# 04_DISCRETE_MIXER_IQ.net
KiCad netlist of a schematic drawn in Altium Designer
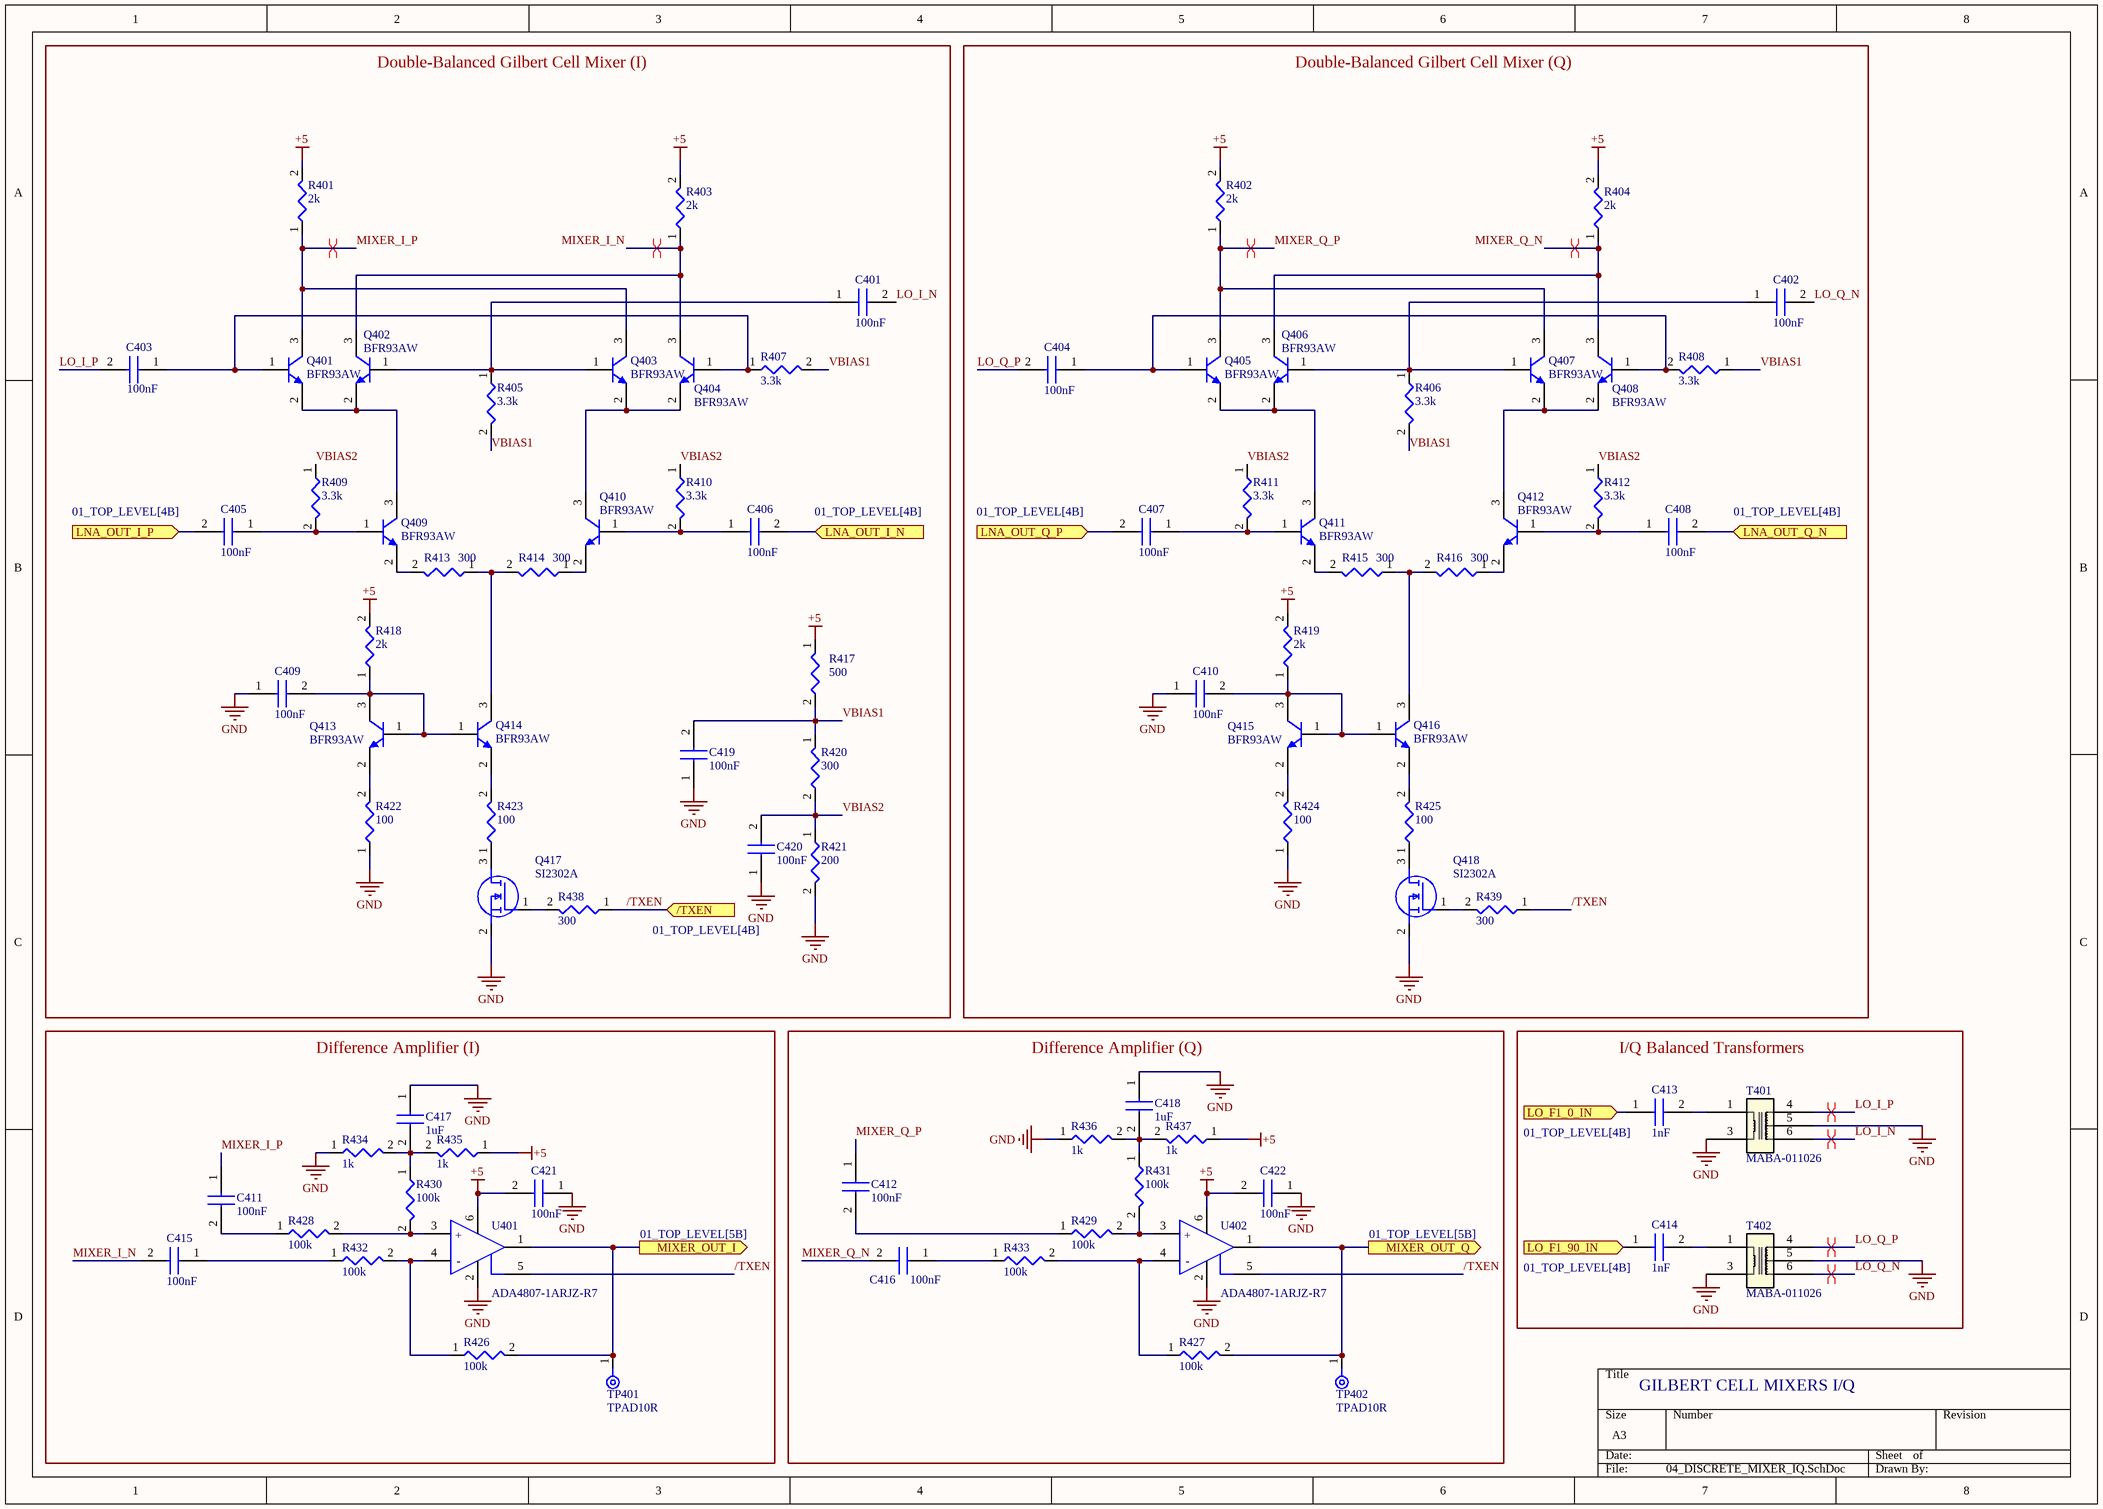
[diagram p0: 04_DISCRETE_MIXER_IQ.SchDoc]

(export (version "E")
  (design (tool "Eeschema 10.0.6"))
  (components
    (comp (ref "C401")
      (value "100nF")
      (footprint "CAP_0805")
      (description "Capacitor SMD 0805")
      (libsource (lib "Passive_Components") (part "CAP_0805"))
    )
    (comp (ref "C402")
      (value "100nF")
      (footprint "CAP_0805")
      (description "Capacitor SMD 0805")
      (libsource (lib "Passive_Components") (part "CAP_0805"))
    )
    (comp (ref "C403")
      (value "100nF")
      (footprint "CAP_0805")
      (description "Capacitor SMD 0805")
      (libsource (lib "Passive_Components") (part "CAP_0805"))
    )
    (comp (ref "C404")
      (value "100nF")
      (footprint "CAP_0805")
      (description "Capacitor SMD 0805")
      (libsource (lib "Passive_Components") (part "CAP_0805"))
    )
    (comp (ref "C405")
      (value "100nF")
      (footprint "CAP_0805")
      (description "Capacitor SMD 0805")
      (libsource (lib "Passive_Components") (part "CAP_0805"))
    )
    (comp (ref "C406")
      (value "100nF")
      (footprint "CAP_0805")
      (description "Capacitor SMD 0805")
      (libsource (lib "Passive_Components") (part "CAP_0805"))
    )
    (comp (ref "C407")
      (value "100nF")
      (footprint "CAP_0805")
      (description "Capacitor SMD 0805")
      (libsource (lib "Passive_Components") (part "CAP_0805"))
    )
    (comp (ref "C408")
      (value "100nF")
      (footprint "CAP_0805")
      (description "Capacitor SMD 0805")
      (libsource (lib "Passive_Components") (part "CAP_0805"))
    )
    (comp (ref "C409")
      (value "100nF")
      (footprint "CAP_0805")
      (description "Capacitor SMD 0805")
      (libsource (lib "Passive_Components") (part "CAP_0805"))
    )
    (comp (ref "C410")
      (value "100nF")
      (footprint "CAP_0805")
      (description "Capacitor SMD 0805")
      (libsource (lib "Passive_Components") (part "CAP_0805"))
    )
    (comp (ref "C411")
      (value "100nF")
      (footprint "CAP_0805")
      (description "Capacitor SMD 0805")
      (libsource (lib "Passive_Components") (part "CAP_0805"))
    )
    (comp (ref "C412")
      (value "100nF")
      (footprint "CAP_0805")
      (description "Capacitor SMD 0805")
      (libsource (lib "Passive_Components") (part "CAP_0805"))
    )
    (comp (ref "C413")
      (value "1nF")
      (footprint "CAP_0805")
      (description "Capacitor SMD 0805")
      (libsource (lib "Passive_Components") (part "CAP_0805"))
    )
    (comp (ref "C414")
      (value "1nF")
      (footprint "CAP_0805")
      (description "Capacitor SMD 0805")
      (libsource (lib "Passive_Components") (part "CAP_0805"))
    )
    (comp (ref "C415")
      (value "100nF")
      (footprint "CAP_0805")
      (description "Capacitor SMD 0805")
      (libsource (lib "Passive_Components") (part "CAP_0805"))
    )
    (comp (ref "C416")
      (value "100nF")
      (footprint "CAP_0805")
      (description "Capacitor SMD 0805")
      (libsource (lib "Passive_Components") (part "CAP_0805"))
    )
    (comp (ref "C417")
      (value "1uF")
      (footprint "CAP_0805")
      (description "Capacitor SMD 0805")
      (libsource (lib "Passive_Components") (part "CAP_0805"))
    )
    (comp (ref "C418")
      (value "1uF")
      (footprint "CAP_0805")
      (description "Capacitor SMD 0805")
      (libsource (lib "Passive_Components") (part "CAP_0805"))
    )
    (comp (ref "C419")
      (value "100nF")
      (footprint "CAP_0805")
      (description "Capacitor SMD 0805")
      (libsource (lib "Passive_Components") (part "CAP_0805"))
    )
    (comp (ref "C420")
      (value "100nF")
      (footprint "CAP_0805")
      (description "Capacitor SMD 0805")
      (libsource (lib "Passive_Components") (part "CAP_0805"))
    )
    (comp (ref "C421")
      (value "100nF")
      (footprint "CAP_0805")
      (description "Capacitor SMD 0805")
      (libsource (lib "Passive_Components") (part "CAP_0805"))
    )
    (comp (ref "C422")
      (value "100nF")
      (footprint "CAP_0805")
      (description "Capacitor SMD 0805")
      (libsource (lib "Passive_Components") (part "CAP_0805"))
    )
    (comp (ref "Q401")
      (value "BFR93AW")
      (footprint "INF-SOT323_M")
      (description "NPN Silicon RF Transistor, 12 V VCEO, 90 mA IC, 15.5 dB Gmax, SOT323, Green")
      (fields (field (name "MANUFACTURER") "Infineon"))
      (libsource (lib "Altium Content Vault") (part "INF-BFR93AW-3"))
    )
    (comp (ref "Q402")
      (value "BFR93AW")
      (footprint "INF-SOT323_M")
      (description "NPN Silicon RF Transistor, 12 V VCEO, 90 mA IC, 15.5 dB Gmax, SOT323, Green")
      (fields (field (name "MANUFACTURER") "Infineon"))
      (libsource (lib "Altium Content Vault") (part "INF-BFR93AW-3"))
    )
    (comp (ref "Q403")
      (value "BFR93AW")
      (footprint "INF-SOT323_M")
      (description "NPN Silicon RF Transistor, 12 V VCEO, 90 mA IC, 15.5 dB Gmax, SOT323, Green")
      (fields (field (name "MANUFACTURER") "Infineon"))
      (libsource (lib "Altium Content Vault") (part "INF-BFR93AW-3"))
    )
    (comp (ref "Q404")
      (value "BFR93AW")
      (footprint "INF-SOT323_M")
      (description "NPN Silicon RF Transistor, 12 V VCEO, 90 mA IC, 15.5 dB Gmax, SOT323, Green")
      (fields (field (name "MANUFACTURER") "Infineon"))
      (libsource (lib "Altium Content Vault") (part "INF-BFR93AW-3"))
    )
    (comp (ref "Q405")
      (value "BFR93AW")
      (footprint "INF-SOT323_M")
      (description "NPN Silicon RF Transistor, 12 V VCEO, 90 mA IC, 15.5 dB Gmax, SOT323, Green")
      (fields (field (name "MANUFACTURER") "Infineon"))
      (libsource (lib "Altium Content Vault") (part "INF-BFR93AW-3"))
    )
    (comp (ref "Q406")
      (value "BFR93AW")
      (footprint "INF-SOT323_M")
      (description "NPN Silicon RF Transistor, 12 V VCEO, 90 mA IC, 15.5 dB Gmax, SOT323, Green")
      (fields (field (name "MANUFACTURER") "Infineon"))
      (libsource (lib "Altium Content Vault") (part "INF-BFR93AW-3"))
    )
    (comp (ref "Q407")
      (value "BFR93AW")
      (footprint "INF-SOT323_M")
      (description "NPN Silicon RF Transistor, 12 V VCEO, 90 mA IC, 15.5 dB Gmax, SOT323, Green")
      (fields (field (name "MANUFACTURER") "Infineon"))
      (libsource (lib "Altium Content Vault") (part "INF-BFR93AW-3"))
    )
    (comp (ref "Q408")
      (value "BFR93AW")
      (footprint "INF-SOT323_M")
      (description "NPN Silicon RF Transistor, 12 V VCEO, 90 mA IC, 15.5 dB Gmax, SOT323, Green")
      (fields (field (name "MANUFACTURER") "Infineon"))
      (libsource (lib "Altium Content Vault") (part "INF-BFR93AW-3"))
    )
    (comp (ref "Q409")
      (value "BFR93AW")
      (footprint "INF-SOT323_M")
      (description "NPN Silicon RF Transistor, 12 V VCEO, 90 mA IC, 15.5 dB Gmax, SOT323, Green")
      (fields (field (name "MANUFACTURER") "Infineon"))
      (libsource (lib "Altium Content Vault") (part "INF-BFR93AW-3"))
    )
    (comp (ref "Q410")
      (value "BFR93AW")
      (footprint "INF-SOT323_M")
      (description "NPN Silicon RF Transistor, 12 V VCEO, 90 mA IC, 15.5 dB Gmax, SOT323, Green")
      (fields (field (name "MANUFACTURER") "Infineon"))
      (libsource (lib "Altium Content Vault") (part "INF-BFR93AW-3"))
    )
    (comp (ref "Q411")
      (value "BFR93AW")
      (footprint "INF-SOT323_M")
      (description "NPN Silicon RF Transistor, 12 V VCEO, 90 mA IC, 15.5 dB Gmax, SOT323, Green")
      (fields (field (name "MANUFACTURER") "Infineon"))
      (libsource (lib "Altium Content Vault") (part "INF-BFR93AW-3"))
    )
    (comp (ref "Q412")
      (value "BFR93AW")
      (footprint "INF-SOT323_M")
      (description "NPN Silicon RF Transistor, 12 V VCEO, 90 mA IC, 15.5 dB Gmax, SOT323, Green")
      (fields (field (name "MANUFACTURER") "Infineon"))
      (libsource (lib "Altium Content Vault") (part "INF-BFR93AW-3"))
    )
    (comp (ref "Q413")
      (value "BFR93AW")
      (footprint "INF-SOT323_M")
      (description "NPN Silicon RF Transistor, 12 V VCEO, 90 mA IC, 15.5 dB Gmax, SOT323, Green")
      (fields (field (name "MANUFACTURER") "Infineon"))
      (libsource (lib "Altium Content Vault") (part "INF-BFR93AW-3"))
    )
    (comp (ref "Q414")
      (value "BFR93AW")
      (footprint "INF-SOT323_M")
      (description "NPN Silicon RF Transistor, 12 V VCEO, 90 mA IC, 15.5 dB Gmax, SOT323, Green")
      (fields (field (name "MANUFACTURER") "Infineon"))
      (libsource (lib "Altium Content Vault") (part "INF-BFR93AW-3"))
    )
    (comp (ref "Q415")
      (value "BFR93AW")
      (footprint "INF-SOT323_M")
      (description "NPN Silicon RF Transistor, 12 V VCEO, 90 mA IC, 15.5 dB Gmax, SOT323, Green")
      (fields (field (name "MANUFACTURER") "Infineon"))
      (libsource (lib "Altium Content Vault") (part "INF-BFR93AW-3"))
    )
    (comp (ref "Q416")
      (value "BFR93AW")
      (footprint "INF-SOT323_M")
      (description "NPN Silicon RF Transistor, 12 V VCEO, 90 mA IC, 15.5 dB Gmax, SOT323, Green")
      (fields (field (name "MANUFACTURER") "Infineon"))
      (libsource (lib "Altium Content Vault") (part "INF-BFR93AW-3"))
    )
    (comp (ref "Q417")
      (value "SI2302A")
      (footprint "SamacSys:SOT95P237X112-3N")
      (description "MOSFET (N-Channel)")
      (libsource (lib "*") (part "SI2302ADS"))
    )
    (comp (ref "Q418")
      (value "SI2302A")
      (footprint "SamacSys:SOT95P237X112-3N")
      (description "MOSFET (N-Channel)")
      (libsource (lib "*") (part "SI2302ADS"))
    )
    (comp (ref "R401")
      (value "2k")
      (footprint "RES_0805")
      (description "Resistor SMD 0805")
      (libsource (lib "Passive_Components") (part "RES_0805"))
    )
    (comp (ref "R402")
      (value "2k")
      (footprint "RES_0805")
      (description "Resistor SMD 0805")
      (libsource (lib "Passive_Components") (part "RES_0805"))
    )
    (comp (ref "R403")
      (value "2k")
      (footprint "RES_0805")
      (description "Resistor SMD 0805")
      (libsource (lib "Passive_Components") (part "RES_0805"))
    )
    (comp (ref "R404")
      (value "2k")
      (footprint "RES_0805")
      (description "Resistor SMD 0805")
      (libsource (lib "Passive_Components") (part "RES_0805"))
    )
    (comp (ref "R405")
      (value "3.3k")
      (footprint "RES_0805")
      (description "Resistor SMD 0805")
      (libsource (lib "Passive_Components") (part "RES_0805"))
    )
    (comp (ref "R406")
      (value "3.3k")
      (footprint "RES_0805")
      (description "Resistor SMD 0805")
      (libsource (lib "Passive_Components") (part "RES_0805"))
    )
    (comp (ref "R407")
      (value "3.3k")
      (footprint "RES_0805")
      (description "Resistor SMD 0805")
      (libsource (lib "Passive_Components") (part "RES_0805"))
    )
    (comp (ref "R408")
      (value "3.3k")
      (footprint "RES_0805")
      (description "Resistor SMD 0805")
      (libsource (lib "Passive_Components") (part "RES_0805"))
    )
    (comp (ref "R409")
      (value "3.3k")
      (footprint "RES_0805")
      (description "Resistor SMD 0805")
      (libsource (lib "Passive_Components") (part "RES_0805"))
    )
    (comp (ref "R410")
      (value "3.3k")
      (footprint "RES_0805")
      (description "Resistor SMD 0805")
      (libsource (lib "Passive_Components") (part "RES_0805"))
    )
    (comp (ref "R411")
      (value "3.3k")
      (footprint "RES_0805")
      (description "Resistor SMD 0805")
      (libsource (lib "Passive_Components") (part "RES_0805"))
    )
    (comp (ref "R412")
      (value "3.3k")
      (footprint "RES_0805")
      (description "Resistor SMD 0805")
      (libsource (lib "Passive_Components") (part "RES_0805"))
    )
    (comp (ref "R413")
      (value "300")
      (footprint "RES_0805")
      (description "Resistor SMD 0805")
      (libsource (lib "Passive_Components") (part "RES_0805"))
    )
    (comp (ref "R414")
      (value "300")
      (footprint "RES_0805")
      (description "Resistor SMD 0805")
      (libsource (lib "Passive_Components") (part "RES_0805"))
    )
    (comp (ref "R415")
      (value "300")
      (footprint "RES_0805")
      (description "Resistor SMD 0805")
      (libsource (lib "Passive_Components") (part "RES_0805"))
    )
    (comp (ref "R416")
      (value "300")
      (footprint "RES_0805")
      (description "Resistor SMD 0805")
      (libsource (lib "Passive_Components") (part "RES_0805"))
    )
    (comp (ref "R417")
      (value "500")
      (footprint "RES_0805")
      (description "Resistor SMD 0805")
      (libsource (lib "Passive_Components") (part "RES_0805"))
    )
    (comp (ref "R418")
      (value "2k")
      (footprint "RES_0805")
      (description "Resistor SMD 0805")
      (libsource (lib "Passive_Components") (part "RES_0805"))
    )
    (comp (ref "R419")
      (value "2k")
      (footprint "RES_0805")
      (description "Resistor SMD 0805")
      (libsource (lib "Passive_Components") (part "RES_0805"))
    )
    (comp (ref "R420")
      (value "300")
      (footprint "RES_0805")
      (description "Resistor SMD 0805")
      (libsource (lib "Passive_Components") (part "RES_0805"))
    )
    (comp (ref "R421")
      (value "200")
      (footprint "RES_0805")
      (description "Resistor SMD 0805")
      (libsource (lib "Passive_Components") (part "RES_0805"))
    )
    (comp (ref "R422")
      (value "100")
      (footprint "RES_0805")
      (description "Resistor SMD 0805")
      (libsource (lib "Passive_Components") (part "RES_0805"))
    )
    (comp (ref "R423")
      (value "100")
      (footprint "RES_0805")
      (description "Resistor SMD 0805")
      (libsource (lib "Passive_Components") (part "RES_0805"))
    )
    (comp (ref "R424")
      (value "100")
      (footprint "RES_0805")
      (description "Resistor SMD 0805")
      (libsource (lib "Passive_Components") (part "RES_0805"))
    )
    (comp (ref "R425")
      (value "100")
      (footprint "RES_0805")
      (description "Resistor SMD 0805")
      (libsource (lib "Passive_Components") (part "RES_0805"))
    )
    (comp (ref "R426")
      (value "100k")
      (footprint "RES_0805")
      (description "Resistor SMD 0805")
      (libsource (lib "Passive_Components") (part "RES_0805"))
    )
    (comp (ref "R427")
      (value "100k")
      (footprint "RES_0805")
      (description "Resistor SMD 0805")
      (libsource (lib "Passive_Components") (part "RES_0805"))
    )
    (comp (ref "R428")
      (value "100k")
      (footprint "RES_0805")
      (description "Resistor SMD 0805")
      (libsource (lib "Passive_Components") (part "RES_0805"))
    )
    (comp (ref "R429")
      (value "100k")
      (footprint "RES_0805")
      (description "Resistor SMD 0805")
      (libsource (lib "Passive_Components") (part "RES_0805"))
    )
    (comp (ref "R430")
      (value "100k")
      (footprint "RES_0805")
      (description "Resistor SMD 0805")
      (libsource (lib "Passive_Components") (part "RES_0805"))
    )
    (comp (ref "R431")
      (value "100k")
      (footprint "RES_0805")
      (description "Resistor SMD 0805")
      (libsource (lib "Passive_Components") (part "RES_0805"))
    )
    (comp (ref "R432")
      (value "100k")
      (footprint "RES_0805")
      (description "Resistor SMD 0805")
      (libsource (lib "Passive_Components") (part "RES_0805"))
    )
    (comp (ref "R433")
      (value "100k")
      (footprint "RES_0805")
      (description "Resistor SMD 0805")
      (libsource (lib "Passive_Components") (part "RES_0805"))
    )
    (comp (ref "R434")
      (value "1k")
      (footprint "RES_0805")
      (description "Resistor SMD 0805")
      (libsource (lib "Passive_Components") (part "RES_0805"))
    )
    (comp (ref "R435")
      (value "1k")
      (footprint "RES_0805")
      (description "Resistor SMD 0805")
      (libsource (lib "Passive_Components") (part "RES_0805"))
    )
    (comp (ref "R436")
      (value "1k")
      (footprint "RES_0805")
      (description "Resistor SMD 0805")
      (libsource (lib "Passive_Components") (part "RES_0805"))
    )
    (comp (ref "R437")
      (value "1k")
      (footprint "RES_0805")
      (description "Resistor SMD 0805")
      (libsource (lib "Passive_Components") (part "RES_0805"))
    )
    (comp (ref "R438")
      (value "300")
      (footprint "RES_0805")
      (description "Resistor SMD 0805")
      (libsource (lib "Passive_Components") (part "RES_0805"))
    )
    (comp (ref "R439")
      (value "300")
      (footprint "RES_0805")
      (description "Resistor SMD 0805")
      (libsource (lib "Passive_Components") (part "RES_0805"))
    )
    (comp (ref "T401")
      (value "MABA-011026")
      (footprint "MABA-011026_MCM")
      (description "RF Transformer")
      (fields (field (name "COPYRIGHT") "Copyright (C) 2025 Ultra Librarian. All rights reserved."))
      (libsource (lib "PASSIVE_COMPONENTS") (part "MABA-011026"))
    )
    (comp (ref "T402")
      (value "MABA-011026")
      (footprint "MABA-011026_MCM")
      (description "RF Transformer")
      (fields (field (name "COPYRIGHT") "Copyright (C) 2025 Ultra Librarian. All rights reserved."))
      (libsource (lib "PASSIVE_COMPONENTS") (part "MABA-011026"))
    )
    (comp (ref "TP401")
      (value "TPAD10R")
      (footprint "TEST_POINT")
      (description "Testpont Pad 10R")
      (libsource (lib "PASSIVE_COMPONENTS") (part "TEST_POINT"))
    )
    (comp (ref "TP402")
      (value "TPAD10R")
      (footprint "TEST_POINT")
      (description "Testpont Pad 10R")
      (libsource (lib "PASSIVE_COMPONENTS") (part "TEST_POINT"))
    )
    (comp (ref "U401")
      (value "ADA4807-1ARJZ-R7")
      (footprint "FP-RJ-6-IPC_A")
      (description "IC OPAMP VFB 1 CIRCUIT SOT23-6")
      (libsource (lib "Altium Content Vault") (part "0cc169e61f44c0172c2773b4ba3b2c6"))
    )
    (comp (ref "U402")
      (value "ADA4807-1ARJZ-R7")
      (footprint "FP-RJ-6-IPC_A")
      (description "IC OPAMP VFB 1 CIRCUIT SOT23-6")
      (libsource (lib "Altium Content Vault") (part "0cc169e61f44c0172c2773b4ba3b2c6"))
    )
  )
  (nets
    (net (code "1") (name "+5") (class "Default")
      (node (ref "C421") (pin "2") (pinfunction "2_2") (pintype "passive"))
      (node (ref "C422") (pin "2") (pinfunction "2_2") (pintype "passive"))
      (node (ref "R401") (pin "2") (pinfunction "2_2") (pintype "passive"))
      (node (ref "R402") (pin "2") (pinfunction "2_2") (pintype "passive"))
      (node (ref "R403") (pin "2") (pinfunction "2_2") (pintype "passive"))
      (node (ref "R404") (pin "2") (pinfunction "2_2") (pintype "passive"))
      (node (ref "R417") (pin "1") (pinfunction "1_1") (pintype "passive"))
      (node (ref "R418") (pin "2") (pinfunction "2_2") (pintype "passive"))
      (node (ref "R419") (pin "2") (pinfunction "2_2") (pintype "passive"))
      (node (ref "R435") (pin "1") (pinfunction "1_1") (pintype "passive"))
      (node (ref "R437") (pin "1") (pinfunction "1_1") (pintype "passive"))
      (node (ref "U401") (pin "6") (pinfunction "+VS_6") (pintype "power_in"))
      (node (ref "U402") (pin "6") (pinfunction "+VS_6") (pintype "power_in"))
    )
    (net (code "2") (name "/LNA_OUT_I_N") (class "Default")
      (node (ref "C406") (pin "2") (pinfunction "2_2") (pintype "passive"))
    )
    (net (code "3") (name "/LNA_OUT_I_P") (class "Default")
      (node (ref "C405") (pin "2") (pinfunction "2_2") (pintype "passive"))
    )
    (net (code "4") (name "/LNA_OUT_Q_N") (class "Default")
      (node (ref "C408") (pin "2") (pinfunction "2_2") (pintype "passive"))
    )
    (net (code "5") (name "/LNA_OUT_Q_P") (class "Default")
      (node (ref "C407") (pin "2") (pinfunction "2_2") (pintype "passive"))
    )
    (net (code "6") (name "/LO_F1_0_IN") (class "Default")
      (node (ref "C413") (pin "1") (pinfunction "1_1") (pintype "passive"))
    )
    (net (code "7") (name "/LO_F1_90_IN") (class "Default")
      (node (ref "C414") (pin "1") (pinfunction "1_1") (pintype "passive"))
    )
    (net (code "8") (name "/LO_I_N") (class "Default")
      (node (ref "C401") (pin "2") (pinfunction "2_2") (pintype "passive"))
      (node (ref "T401") (pin "6") (pinfunction "6_6") (pintype "passive"))
    )
    (net (code "9") (name "/LO_I_P") (class "Default")
      (node (ref "C403") (pin "2") (pinfunction "2_2") (pintype "passive"))
      (node (ref "T401") (pin "4") (pinfunction "4_4") (pintype "passive"))
    )
    (net (code "10") (name "/LO_Q_N") (class "Default")
      (node (ref "C402") (pin "2") (pinfunction "2_2") (pintype "passive"))
      (node (ref "T402") (pin "6") (pinfunction "6_6") (pintype "passive"))
    )
    (net (code "11") (name "/LO_Q_P") (class "Default")
      (node (ref "C404") (pin "2") (pinfunction "2_2") (pintype "passive"))
      (node (ref "T402") (pin "4") (pinfunction "4_4") (pintype "passive"))
    )
    (net (code "12") (name "/MIXER_I_N") (class "Default")
      (node (ref "C415") (pin "2") (pinfunction "2_2") (pintype "passive"))
      (node (ref "Q402") (pin "3") (pinfunction "C_3") (pintype "passive"))
      (node (ref "Q404") (pin "3") (pinfunction "C_3") (pintype "passive"))
      (node (ref "R403") (pin "1") (pinfunction "1_1") (pintype "passive"))
    )
    (net (code "13") (name "/MIXER_I_P") (class "Default")
      (node (ref "C411") (pin "1") (pinfunction "1_1") (pintype "passive"))
      (node (ref "Q401") (pin "3") (pinfunction "C_3") (pintype "passive"))
      (node (ref "Q403") (pin "3") (pinfunction "C_3") (pintype "passive"))
      (node (ref "R401") (pin "1") (pinfunction "1_1") (pintype "passive"))
    )
    (net (code "14") (name "/MIXER_OUT_I") (class "Default")
      (node (ref "R426") (pin "2") (pinfunction "2_2") (pintype "passive"))
      (node (ref "TP401") (pin "1") (pinfunction "1_1") (pintype "passive"))
      (node (ref "U401") (pin "1") (pinfunction "VOUT_1") (pintype "passive"))
    )
    (net (code "15") (name "/MIXER_OUT_Q") (class "Default")
      (node (ref "R427") (pin "2") (pinfunction "2_2") (pintype "passive"))
      (node (ref "TP402") (pin "1") (pinfunction "1_1") (pintype "passive"))
      (node (ref "U402") (pin "1") (pinfunction "VOUT_1") (pintype "passive"))
    )
    (net (code "16") (name "/MIXER_Q_N") (class "Default")
      (node (ref "C416") (pin "2") (pinfunction "2_2") (pintype "passive"))
      (node (ref "Q406") (pin "3") (pinfunction "C_3") (pintype "passive"))
      (node (ref "Q408") (pin "3") (pinfunction "C_3") (pintype "passive"))
      (node (ref "R404") (pin "1") (pinfunction "1_1") (pintype "passive"))
    )
    (net (code "17") (name "/MIXER_Q_P") (class "Default")
      (node (ref "C412") (pin "1") (pinfunction "1_1") (pintype "passive"))
      (node (ref "Q405") (pin "3") (pinfunction "C_3") (pintype "passive"))
      (node (ref "Q407") (pin "3") (pinfunction "C_3") (pintype "passive"))
      (node (ref "R402") (pin "1") (pinfunction "1_1") (pintype "passive"))
    )
    (net (code "18") (name "/VBIAS1") (class "Default")
      (node (ref "C419") (pin "2") (pinfunction "2_2") (pintype "passive"))
      (node (ref "R405") (pin "2") (pinfunction "2_2") (pintype "passive"))
      (node (ref "R406") (pin "2") (pinfunction "2_2") (pintype "passive"))
      (node (ref "R407") (pin "2") (pinfunction "2_2") (pintype "passive"))
      (node (ref "R408") (pin "1") (pinfunction "1_1") (pintype "passive"))
      (node (ref "R417") (pin "2") (pinfunction "2_2") (pintype "passive"))
      (node (ref "R420") (pin "1") (pinfunction "1_1") (pintype "passive"))
    )
    (net (code "19") (name "/VBIAS2") (class "Default")
      (node (ref "C420") (pin "2") (pinfunction "2_2") (pintype "passive"))
      (node (ref "R409") (pin "1") (pinfunction "1_1") (pintype "passive"))
      (node (ref "R410") (pin "1") (pinfunction "1_1") (pintype "passive"))
      (node (ref "R411") (pin "1") (pinfunction "1_1") (pintype "passive"))
      (node (ref "R412") (pin "1") (pinfunction "1_1") (pintype "passive"))
      (node (ref "R420") (pin "2") (pinfunction "2_2") (pintype "passive"))
      (node (ref "R421") (pin "1") (pinfunction "1_1") (pintype "passive"))
    )
    (net (code "20") (name "/{slash}TXEN") (class "Default")
      (node (ref "R438") (pin "1") (pinfunction "1_1") (pintype "passive"))
      (node (ref "R439") (pin "1") (pinfunction "1_1") (pintype "passive"))
      (node (ref "U401") (pin "5") (pinfunction "~{DISABLE}_5") (pintype "passive"))
      (node (ref "U402") (pin "5") (pinfunction "~{DISABLE}_5") (pintype "passive"))
    )
    (net (code "21") (name "GND") (class "Default")
      (node (ref "C409") (pin "1") (pinfunction "1_1") (pintype "passive"))
      (node (ref "C410") (pin "1") (pinfunction "1_1") (pintype "passive"))
      (node (ref "C417") (pin "1") (pinfunction "1_1") (pintype "passive"))
      (node (ref "C418") (pin "1") (pinfunction "1_1") (pintype "passive"))
      (node (ref "C419") (pin "1") (pinfunction "1_1") (pintype "passive"))
      (node (ref "C420") (pin "1") (pinfunction "1_1") (pintype "passive"))
      (node (ref "C421") (pin "1") (pinfunction "1_1") (pintype "passive"))
      (node (ref "C422") (pin "1") (pinfunction "1_1") (pintype "passive"))
      (node (ref "Q417") (pin "2") (pinfunction "S_2") (pintype "passive"))
      (node (ref "Q418") (pin "2") (pinfunction "S_2") (pintype "passive"))
      (node (ref "R421") (pin "2") (pinfunction "2_2") (pintype "passive"))
      (node (ref "R422") (pin "1") (pinfunction "1_1") (pintype "passive"))
      (node (ref "R424") (pin "1") (pinfunction "1_1") (pintype "passive"))
      (node (ref "R434") (pin "1") (pinfunction "1_1") (pintype "passive"))
      (node (ref "R436") (pin "1") (pinfunction "1_1") (pintype "passive"))
      (node (ref "T401") (pin "3") (pinfunction "3_3") (pintype "passive"))
      (node (ref "T401") (pin "5") (pinfunction "5_5") (pintype "passive"))
      (node (ref "T402") (pin "3") (pinfunction "3_3") (pintype "passive"))
      (node (ref "T402") (pin "5") (pinfunction "5_5") (pintype "passive"))
      (node (ref "U401") (pin "2") (pinfunction "-VS_2") (pintype "power_in"))
      (node (ref "U402") (pin "2") (pinfunction "-VS_2") (pintype "power_in"))
    )
    (net (code "22") (name "Net-(C411-Pad2)") (class "Default")
      (node (ref "C411") (pin "2") (pinfunction "2_2") (pintype "passive"))
      (node (ref "R428") (pin "1") (pinfunction "1_1") (pintype "passive"))
    )
    (net (code "23") (name "Net-(C412-Pad2)") (class "Default")
      (node (ref "C412") (pin "2") (pinfunction "2_2") (pintype "passive"))
      (node (ref "R429") (pin "1") (pinfunction "1_1") (pintype "passive"))
    )
    (net (code "24") (name "Net-(C413-Pad2)") (class "Default")
      (node (ref "C413") (pin "2") (pinfunction "2_2") (pintype "passive"))
      (node (ref "T401") (pin "1") (pinfunction "1_1") (pintype "passive"))
    )
    (net (code "25") (name "Net-(C414-Pad2)") (class "Default")
      (node (ref "C414") (pin "2") (pinfunction "2_2") (pintype "passive"))
      (node (ref "T402") (pin "1") (pinfunction "1_1") (pintype "passive"))
    )
    (net (code "26") (name "Net-(C415-Pad1)") (class "Default")
      (node (ref "C415") (pin "1") (pinfunction "1_1") (pintype "passive"))
      (node (ref "R432") (pin "1") (pinfunction "1_1") (pintype "passive"))
    )
    (net (code "27") (name "Net-(C416-Pad1)") (class "Default")
      (node (ref "C416") (pin "1") (pinfunction "1_1") (pintype "passive"))
      (node (ref "R433") (pin "1") (pinfunction "1_1") (pintype "passive"))
    )
    (net (code "28") (name "Net-(C417-Pad2)") (class "Default")
      (node (ref "C417") (pin "2") (pinfunction "2_2") (pintype "passive"))
      (node (ref "R430") (pin "1") (pinfunction "1_1") (pintype "passive"))
      (node (ref "R434") (pin "2") (pinfunction "2_2") (pintype "passive"))
      (node (ref "R435") (pin "2") (pinfunction "2_2") (pintype "passive"))
    )
    (net (code "29") (name "Net-(C418-Pad2)") (class "Default")
      (node (ref "C418") (pin "2") (pinfunction "2_2") (pintype "passive"))
      (node (ref "R431") (pin "1") (pinfunction "1_1") (pintype "passive"))
      (node (ref "R436") (pin "2") (pinfunction "2_2") (pintype "passive"))
      (node (ref "R437") (pin "2") (pinfunction "2_2") (pintype "passive"))
    )
    (net (code "30") (name "Net-(Q401-B)") (class "Default")
      (node (ref "C403") (pin "1") (pinfunction "1_1") (pintype "passive"))
      (node (ref "Q401") (pin "1") (pinfunction "B_1") (pintype "passive"))
      (node (ref "Q404") (pin "1") (pinfunction "B_1") (pintype "passive"))
      (node (ref "R407") (pin "1") (pinfunction "1_1") (pintype "passive"))
    )
    (net (code "31") (name "Net-(Q401-E)") (class "Default")
      (node (ref "Q401") (pin "2") (pinfunction "E_2") (pintype "passive"))
      (node (ref "Q402") (pin "2") (pinfunction "E_2") (pintype "passive"))
      (node (ref "Q409") (pin "3") (pinfunction "C_3") (pintype "passive"))
    )
    (net (code "32") (name "Net-(Q402-B)") (class "Default")
      (node (ref "C401") (pin "1") (pinfunction "1_1") (pintype "passive"))
      (node (ref "Q402") (pin "1") (pinfunction "B_1") (pintype "passive"))
      (node (ref "Q403") (pin "1") (pinfunction "B_1") (pintype "passive"))
      (node (ref "R405") (pin "1") (pinfunction "1_1") (pintype "passive"))
    )
    (net (code "33") (name "Net-(Q403-E)") (class "Default")
      (node (ref "Q403") (pin "2") (pinfunction "E_2") (pintype "passive"))
      (node (ref "Q404") (pin "2") (pinfunction "E_2") (pintype "passive"))
      (node (ref "Q410") (pin "3") (pinfunction "C_3") (pintype "passive"))
    )
    (net (code "34") (name "Net-(Q405-B)") (class "Default")
      (node (ref "C404") (pin "1") (pinfunction "1_1") (pintype "passive"))
      (node (ref "Q405") (pin "1") (pinfunction "B_1") (pintype "passive"))
      (node (ref "Q408") (pin "1") (pinfunction "B_1") (pintype "passive"))
      (node (ref "R408") (pin "2") (pinfunction "2_2") (pintype "passive"))
    )
    (net (code "35") (name "Net-(Q405-E)") (class "Default")
      (node (ref "Q405") (pin "2") (pinfunction "E_2") (pintype "passive"))
      (node (ref "Q406") (pin "2") (pinfunction "E_2") (pintype "passive"))
      (node (ref "Q411") (pin "3") (pinfunction "C_3") (pintype "passive"))
    )
    (net (code "36") (name "Net-(Q406-B)") (class "Default")
      (node (ref "C402") (pin "1") (pinfunction "1_1") (pintype "passive"))
      (node (ref "Q406") (pin "1") (pinfunction "B_1") (pintype "passive"))
      (node (ref "Q407") (pin "1") (pinfunction "B_1") (pintype "passive"))
      (node (ref "R406") (pin "1") (pinfunction "1_1") (pintype "passive"))
    )
    (net (code "37") (name "Net-(Q407-E)") (class "Default")
      (node (ref "Q407") (pin "2") (pinfunction "E_2") (pintype "passive"))
      (node (ref "Q408") (pin "2") (pinfunction "E_2") (pintype "passive"))
      (node (ref "Q412") (pin "3") (pinfunction "C_3") (pintype "passive"))
    )
    (net (code "38") (name "Net-(Q409-B)") (class "Default")
      (node (ref "C405") (pin "1") (pinfunction "1_1") (pintype "passive"))
      (node (ref "Q409") (pin "1") (pinfunction "B_1") (pintype "passive"))
      (node (ref "R409") (pin "2") (pinfunction "2_2") (pintype "passive"))
    )
    (net (code "39") (name "Net-(Q409-E)") (class "Default")
      (node (ref "Q409") (pin "2") (pinfunction "E_2") (pintype "passive"))
      (node (ref "R413") (pin "2") (pinfunction "2_2") (pintype "passive"))
    )
    (net (code "40") (name "Net-(Q410-B)") (class "Default")
      (node (ref "C406") (pin "1") (pinfunction "1_1") (pintype "passive"))
      (node (ref "Q410") (pin "1") (pinfunction "B_1") (pintype "passive"))
      (node (ref "R410") (pin "2") (pinfunction "2_2") (pintype "passive"))
    )
    (net (code "41") (name "Net-(Q410-E)") (class "Default")
      (node (ref "Q410") (pin "2") (pinfunction "E_2") (pintype "passive"))
      (node (ref "R414") (pin "1") (pinfunction "1_1") (pintype "passive"))
    )
    (net (code "42") (name "Net-(Q411-B)") (class "Default")
      (node (ref "C407") (pin "1") (pinfunction "1_1") (pintype "passive"))
      (node (ref "Q411") (pin "1") (pinfunction "B_1") (pintype "passive"))
      (node (ref "R411") (pin "2") (pinfunction "2_2") (pintype "passive"))
    )
    (net (code "43") (name "Net-(Q411-E)") (class "Default")
      (node (ref "Q411") (pin "2") (pinfunction "E_2") (pintype "passive"))
      (node (ref "R415") (pin "2") (pinfunction "2_2") (pintype "passive"))
    )
    (net (code "44") (name "Net-(Q412-B)") (class "Default")
      (node (ref "C408") (pin "1") (pinfunction "1_1") (pintype "passive"))
      (node (ref "Q412") (pin "1") (pinfunction "B_1") (pintype "passive"))
      (node (ref "R412") (pin "2") (pinfunction "2_2") (pintype "passive"))
    )
    (net (code "45") (name "Net-(Q412-E)") (class "Default")
      (node (ref "Q412") (pin "2") (pinfunction "E_2") (pintype "passive"))
      (node (ref "R416") (pin "1") (pinfunction "1_1") (pintype "passive"))
    )
    (net (code "46") (name "Net-(Q413-B)") (class "Default")
      (node (ref "C409") (pin "2") (pinfunction "2_2") (pintype "passive"))
      (node (ref "Q413") (pin "1") (pinfunction "B_1") (pintype "passive"))
      (node (ref "Q413") (pin "3") (pinfunction "C_3") (pintype "passive"))
      (node (ref "Q414") (pin "1") (pinfunction "B_1") (pintype "passive"))
      (node (ref "R418") (pin "1") (pinfunction "1_1") (pintype "passive"))
    )
    (net (code "47") (name "Net-(Q413-E)") (class "Default")
      (node (ref "Q413") (pin "2") (pinfunction "E_2") (pintype "passive"))
      (node (ref "R422") (pin "2") (pinfunction "2_2") (pintype "passive"))
    )
    (net (code "48") (name "Net-(Q414-C)") (class "Default")
      (node (ref "Q414") (pin "3") (pinfunction "C_3") (pintype "passive"))
      (node (ref "R413") (pin "1") (pinfunction "1_1") (pintype "passive"))
      (node (ref "R414") (pin "2") (pinfunction "2_2") (pintype "passive"))
    )
    (net (code "49") (name "Net-(Q414-E)") (class "Default")
      (node (ref "Q414") (pin "2") (pinfunction "E_2") (pintype "passive"))
      (node (ref "R423") (pin "2") (pinfunction "2_2") (pintype "passive"))
    )
    (net (code "50") (name "Net-(Q415-B)") (class "Default")
      (node (ref "C410") (pin "2") (pinfunction "2_2") (pintype "passive"))
      (node (ref "Q415") (pin "1") (pinfunction "B_1") (pintype "passive"))
      (node (ref "Q415") (pin "3") (pinfunction "C_3") (pintype "passive"))
      (node (ref "Q416") (pin "1") (pinfunction "B_1") (pintype "passive"))
      (node (ref "R419") (pin "1") (pinfunction "1_1") (pintype "passive"))
    )
    (net (code "51") (name "Net-(Q415-E)") (class "Default")
      (node (ref "Q415") (pin "2") (pinfunction "E_2") (pintype "passive"))
      (node (ref "R424") (pin "2") (pinfunction "2_2") (pintype "passive"))
    )
    (net (code "52") (name "Net-(Q416-C)") (class "Default")
      (node (ref "Q416") (pin "3") (pinfunction "C_3") (pintype "passive"))
      (node (ref "R415") (pin "1") (pinfunction "1_1") (pintype "passive"))
      (node (ref "R416") (pin "2") (pinfunction "2_2") (pintype "passive"))
    )
    (net (code "53") (name "Net-(Q416-E)") (class "Default")
      (node (ref "Q416") (pin "2") (pinfunction "E_2") (pintype "passive"))
      (node (ref "R425") (pin "2") (pinfunction "2_2") (pintype "passive"))
    )
    (net (code "54") (name "Net-(Q417-D)") (class "Default")
      (node (ref "Q417") (pin "3") (pinfunction "D_3") (pintype "passive"))
      (node (ref "R423") (pin "1") (pinfunction "1_1") (pintype "passive"))
    )
    (net (code "55") (name "Net-(Q417-G)") (class "Default")
      (node (ref "Q417") (pin "1") (pinfunction "G_1") (pintype "passive"))
      (node (ref "R438") (pin "2") (pinfunction "2_2") (pintype "passive"))
    )
    (net (code "56") (name "Net-(Q418-D)") (class "Default")
      (node (ref "Q418") (pin "3") (pinfunction "D_3") (pintype "passive"))
      (node (ref "R425") (pin "1") (pinfunction "1_1") (pintype "passive"))
    )
    (net (code "57") (name "Net-(Q418-G)") (class "Default")
      (node (ref "Q418") (pin "1") (pinfunction "G_1") (pintype "passive"))
      (node (ref "R439") (pin "2") (pinfunction "2_2") (pintype "passive"))
    )
    (net (code "58") (name "Net-(U401-+IN)") (class "Default")
      (node (ref "R428") (pin "2") (pinfunction "2_2") (pintype "passive"))
      (node (ref "R430") (pin "2") (pinfunction "2_2") (pintype "passive"))
      (node (ref "U401") (pin "3") (pinfunction "+IN_3") (pintype "tri_state"))
    )
    (net (code "59") (name "Net-(U401--IN)") (class "Default")
      (node (ref "R426") (pin "1") (pinfunction "1_1") (pintype "passive"))
      (node (ref "R432") (pin "2") (pinfunction "2_2") (pintype "passive"))
      (node (ref "U401") (pin "4") (pinfunction "-IN_4") (pintype "tri_state"))
    )
    (net (code "60") (name "Net-(U402-+IN)") (class "Default")
      (node (ref "R429") (pin "2") (pinfunction "2_2") (pintype "passive"))
      (node (ref "R431") (pin "2") (pinfunction "2_2") (pintype "passive"))
      (node (ref "U402") (pin "3") (pinfunction "+IN_3") (pintype "tri_state"))
    )
    (net (code "61") (name "Net-(U402--IN)") (class "Default")
      (node (ref "R427") (pin "1") (pinfunction "1_1") (pintype "passive"))
      (node (ref "R433") (pin "2") (pinfunction "2_2") (pintype "passive"))
      (node (ref "U402") (pin "4") (pinfunction "-IN_4") (pintype "tri_state"))
    )
  )
)
